# Mixer.net
KiCad netlist of a schematic drawn in EAGLE
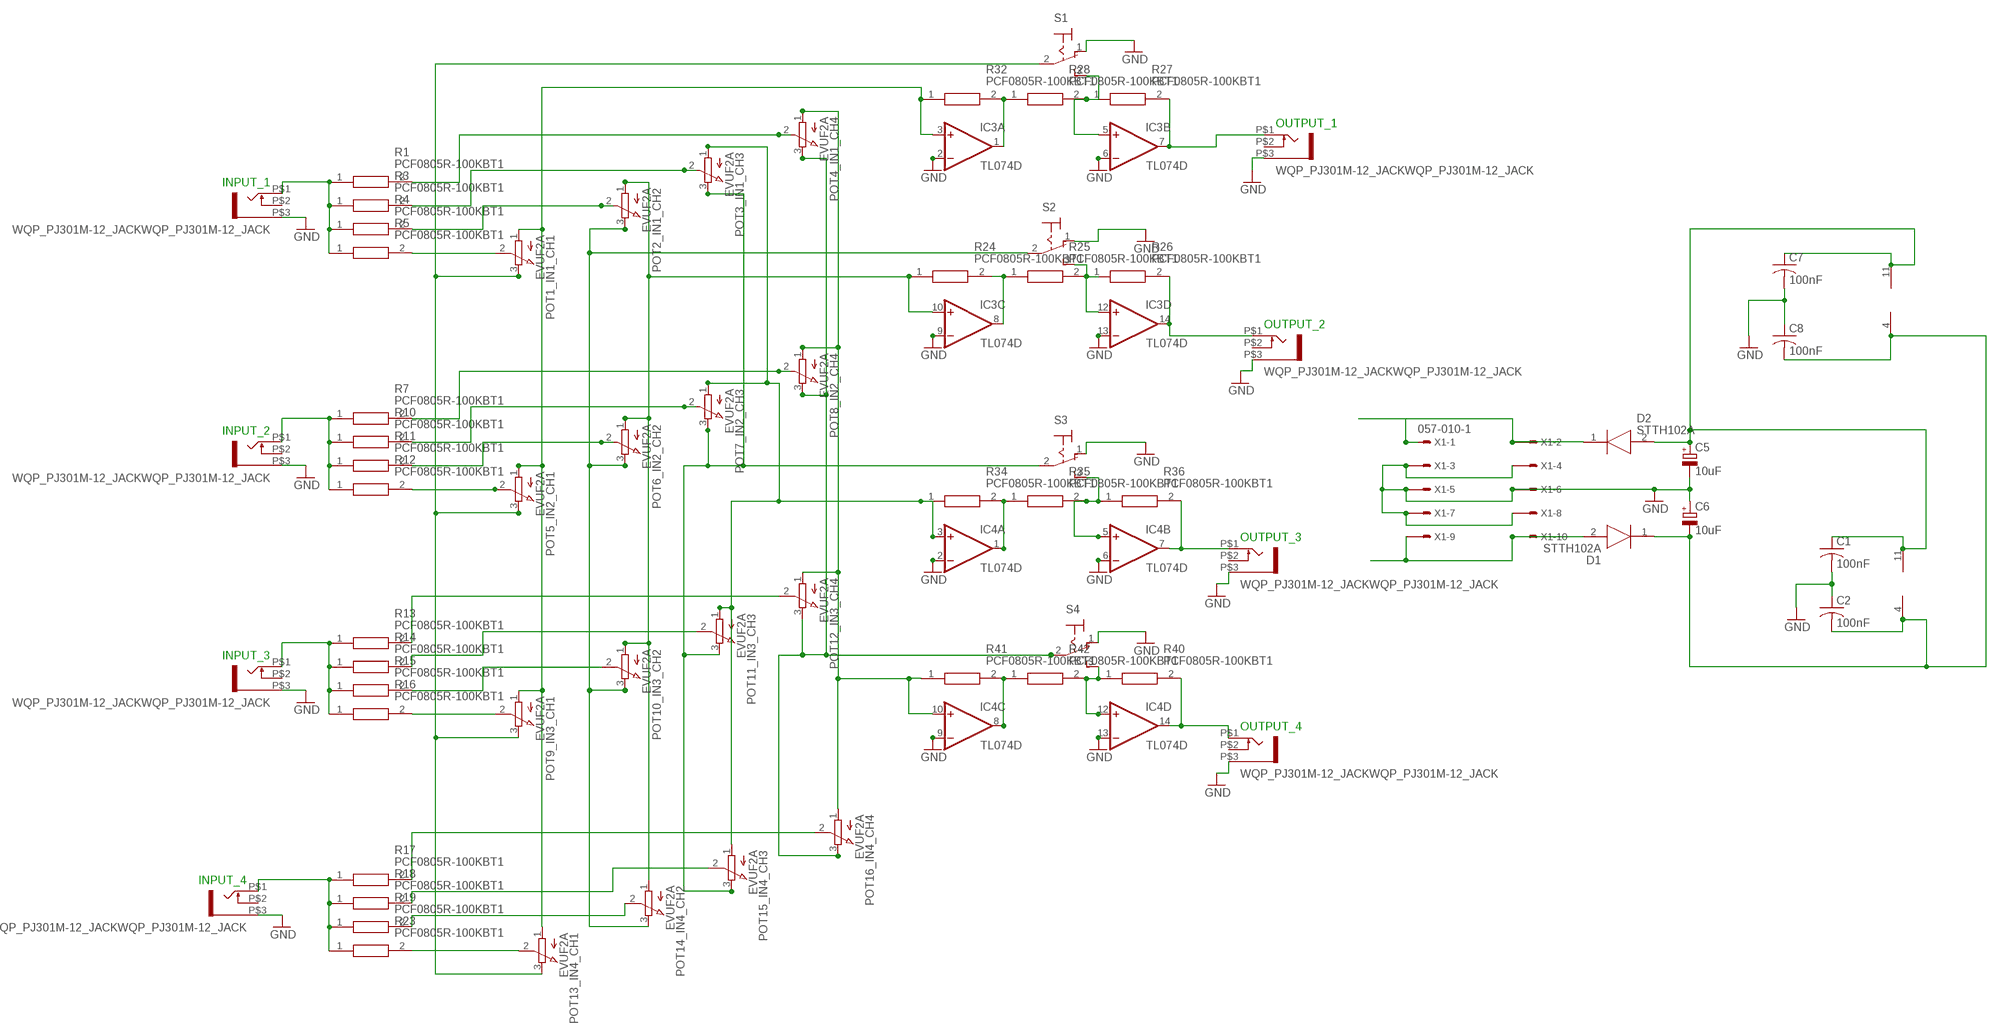
[diagram p0: schematic, sheet 1]

(export (version "E")
  (design (tool "Eeschema 10.0.6"))
  (components
    (comp (ref "C1")
      (value "100nF")
      (footprint "eagle-import:C0805K")
      (libsource (lib "eagle-import") (part "C-USC0805K"))
    )
    (comp (ref "C2")
      (value "100nF")
      (footprint "eagle-import:C0805K")
      (libsource (lib "eagle-import") (part "C-USC0805K"))
    )
    (comp (ref "C5")
      (value "10uF")
      (footprint "eagle-import:153CLV-0605")
      (libsource (lib "eagle-import") (part "CPOL-EU153CLV-0605"))
    )
    (comp (ref "C6")
      (value "10uF")
      (footprint "eagle-import:153CLV-0605")
      (libsource (lib "eagle-import") (part "CPOL-EU153CLV-0605"))
    )
    (comp (ref "C7")
      (value "100nF")
      (footprint "eagle-import:C0805K")
      (libsource (lib "eagle-import") (part "C-USC0805K"))
    )
    (comp (ref "C8")
      (value "100nF")
      (footprint "eagle-import:C0805K")
      (libsource (lib "eagle-import") (part "C-USC0805K"))
    )
    (comp (ref "D1")
      (value "STTH102A")
      (footprint "eagle-import:DIOM5126X265N")
      (libsource (lib "eagle-import") (part "STTH102A"))
    )
    (comp (ref "D2")
      (value "STTH102A")
      (footprint "eagle-import:DIOM5126X265N")
      (libsource (lib "eagle-import") (part "STTH102A"))
    )
    (comp (ref "IC3")
      (value "TL074D")
      (footprint "eagle-import:SO14")
      (libsource (lib "eagle-import") (part "TL074D"))
    )
    (comp (ref "IC4")
      (value "TL074D")
      (footprint "eagle-import:SO14")
      (libsource (lib "eagle-import") (part "TL074D"))
    )
    (comp (ref "INPUT_1")
      (value "WQP_PJ301M-12_JACKWQP_PJ301M-12_JACK")
      (footprint "eagle-import:JACK-3.5")
      (libsource (lib "eagle-import") (part "WQP_PJ301M-12_JACKWQP_PJ301M-12_JACK"))
    )
    (comp (ref "INPUT_2")
      (value "WQP_PJ301M-12_JACKWQP_PJ301M-12_JACK")
      (footprint "eagle-import:JACK-3.5")
      (libsource (lib "eagle-import") (part "WQP_PJ301M-12_JACKWQP_PJ301M-12_JACK"))
    )
    (comp (ref "INPUT_3")
      (value "WQP_PJ301M-12_JACKWQP_PJ301M-12_JACK")
      (footprint "eagle-import:JACK-3.5")
      (libsource (lib "eagle-import") (part "WQP_PJ301M-12_JACKWQP_PJ301M-12_JACK"))
    )
    (comp (ref "INPUT_4")
      (value "WQP_PJ301M-12_JACKWQP_PJ301M-12_JACK")
      (footprint "eagle-import:JACK-3.5")
      (libsource (lib "eagle-import") (part "WQP_PJ301M-12_JACKWQP_PJ301M-12_JACK"))
    )
    (comp (ref "OUTPUT_1")
      (value "WQP_PJ301M-12_JACKWQP_PJ301M-12_JACK")
      (footprint "eagle-import:JACK-3.5")
      (libsource (lib "eagle-import") (part "WQP_PJ301M-12_JACKWQP_PJ301M-12_JACK"))
    )
    (comp (ref "OUTPUT_2")
      (value "WQP_PJ301M-12_JACKWQP_PJ301M-12_JACK")
      (footprint "eagle-import:JACK-3.5")
      (libsource (lib "eagle-import") (part "WQP_PJ301M-12_JACKWQP_PJ301M-12_JACK"))
    )
    (comp (ref "OUTPUT_3")
      (value "WQP_PJ301M-12_JACKWQP_PJ301M-12_JACK")
      (footprint "eagle-import:JACK-3.5")
      (libsource (lib "eagle-import") (part "WQP_PJ301M-12_JACKWQP_PJ301M-12_JACK"))
    )
    (comp (ref "OUTPUT_4")
      (value "WQP_PJ301M-12_JACKWQP_PJ301M-12_JACK")
      (footprint "eagle-import:JACK-3.5")
      (libsource (lib "eagle-import") (part "WQP_PJ301M-12_JACKWQP_PJ301M-12_JACK"))
    )
    (comp (ref "POT1_IN1_CH1")
      (value "EVUF2A")
      (footprint "eagle-import:EVUF")
      (libsource (lib "eagle-import") (part "EVUAF2"))
    )
    (comp (ref "POT2_IN1_CH2")
      (value "EVUF2A")
      (footprint "eagle-import:EVUF")
      (libsource (lib "eagle-import") (part "EVUAF2"))
    )
    (comp (ref "POT3_IN1_CH3")
      (value "EVUF2A")
      (footprint "eagle-import:EVUF")
      (libsource (lib "eagle-import") (part "EVUAF2"))
    )
    (comp (ref "POT4_IN1_CH4")
      (value "EVUF2A")
      (footprint "eagle-import:EVUF")
      (libsource (lib "eagle-import") (part "EVUAF2"))
    )
    (comp (ref "POT5_IN2_CH1")
      (value "EVUF2A")
      (footprint "eagle-import:EVUF")
      (libsource (lib "eagle-import") (part "EVUAF2"))
    )
    (comp (ref "POT6_IN2_CH2")
      (value "EVUF2A")
      (footprint "eagle-import:EVUF")
      (libsource (lib "eagle-import") (part "EVUAF2"))
    )
    (comp (ref "POT7_IN2_CH3")
      (value "EVUF2A")
      (footprint "eagle-import:EVUF")
      (libsource (lib "eagle-import") (part "EVUAF2"))
    )
    (comp (ref "POT8_IN2_CH4")
      (value "EVUF2A")
      (footprint "eagle-import:EVUF")
      (libsource (lib "eagle-import") (part "EVUAF2"))
    )
    (comp (ref "POT9_IN3_CH1")
      (value "EVUF2A")
      (footprint "eagle-import:EVUF")
      (libsource (lib "eagle-import") (part "EVUAF2"))
    )
    (comp (ref "POT10_IN3_CH2")
      (value "EVUF2A")
      (footprint "eagle-import:EVUF")
      (libsource (lib "eagle-import") (part "EVUAF2"))
    )
    (comp (ref "POT11_IN3_CH3")
      (value "EVUF2A")
      (footprint "eagle-import:EVUF")
      (libsource (lib "eagle-import") (part "EVUAF2"))
    )
    (comp (ref "POT12_IN3_CH4")
      (value "EVUF2A")
      (footprint "eagle-import:EVUF")
      (libsource (lib "eagle-import") (part "EVUAF2"))
    )
    (comp (ref "POT13_IN4_CH1")
      (value "EVUF2A")
      (footprint "eagle-import:EVUF")
      (libsource (lib "eagle-import") (part "EVUAF2"))
    )
    (comp (ref "POT14_IN4_CH2")
      (value "EVUF2A")
      (footprint "eagle-import:EVUF")
      (libsource (lib "eagle-import") (part "EVUAF2"))
    )
    (comp (ref "POT15_IN4_CH3")
      (value "EVUF2A")
      (footprint "eagle-import:EVUF")
      (libsource (lib "eagle-import") (part "EVUAF2"))
    )
    (comp (ref "POT16_IN4_CH4")
      (value "EVUF2A")
      (footprint "eagle-import:EVUF")
      (libsource (lib "eagle-import") (part "EVUAF2"))
    )
    (comp (ref "R1")
      (value "PCF0805R-100KBT1")
      (footprint "eagle-import:RESC2012X65N")
      (libsource (lib "eagle-import") (part "PCF0805R-100KBT1"))
    )
    (comp (ref "R3")
      (value "PCF0805R-100KBT1")
      (footprint "eagle-import:RESC2012X65N")
      (libsource (lib "eagle-import") (part "PCF0805R-100KBT1"))
    )
    (comp (ref "R4")
      (value "PCF0805R-100KBT1")
      (footprint "eagle-import:RESC2012X65N")
      (libsource (lib "eagle-import") (part "PCF0805R-100KBT1"))
    )
    (comp (ref "R5")
      (value "PCF0805R-100KBT1")
      (footprint "eagle-import:RESC2012X65N")
      (libsource (lib "eagle-import") (part "PCF0805R-100KBT1"))
    )
    (comp (ref "R7")
      (value "PCF0805R-100KBT1")
      (footprint "eagle-import:RESC2012X65N")
      (libsource (lib "eagle-import") (part "PCF0805R-100KBT1"))
    )
    (comp (ref "R10")
      (value "PCF0805R-100KBT1")
      (footprint "eagle-import:RESC2012X65N")
      (libsource (lib "eagle-import") (part "PCF0805R-100KBT1"))
    )
    (comp (ref "R11")
      (value "PCF0805R-100KBT1")
      (footprint "eagle-import:RESC2012X65N")
      (libsource (lib "eagle-import") (part "PCF0805R-100KBT1"))
    )
    (comp (ref "R12")
      (value "PCF0805R-100KBT1")
      (footprint "eagle-import:RESC2012X65N")
      (libsource (lib "eagle-import") (part "PCF0805R-100KBT1"))
    )
    (comp (ref "R13")
      (value "PCF0805R-100KBT1")
      (footprint "eagle-import:RESC2012X65N")
      (libsource (lib "eagle-import") (part "PCF0805R-100KBT1"))
    )
    (comp (ref "R14")
      (value "PCF0805R-100KBT1")
      (footprint "eagle-import:RESC2012X65N")
      (libsource (lib "eagle-import") (part "PCF0805R-100KBT1"))
    )
    (comp (ref "R15")
      (value "PCF0805R-100KBT1")
      (footprint "eagle-import:RESC2012X65N")
      (libsource (lib "eagle-import") (part "PCF0805R-100KBT1"))
    )
    (comp (ref "R16")
      (value "PCF0805R-100KBT1")
      (footprint "eagle-import:RESC2012X65N")
      (libsource (lib "eagle-import") (part "PCF0805R-100KBT1"))
    )
    (comp (ref "R17")
      (value "PCF0805R-100KBT1")
      (footprint "eagle-import:RESC2012X65N")
      (libsource (lib "eagle-import") (part "PCF0805R-100KBT1"))
    )
    (comp (ref "R18")
      (value "PCF0805R-100KBT1")
      (footprint "eagle-import:RESC2012X65N")
      (libsource (lib "eagle-import") (part "PCF0805R-100KBT1"))
    )
    (comp (ref "R19")
      (value "PCF0805R-100KBT1")
      (footprint "eagle-import:RESC2012X65N")
      (libsource (lib "eagle-import") (part "PCF0805R-100KBT1"))
    )
    (comp (ref "R23")
      (value "PCF0805R-100KBT1")
      (footprint "eagle-import:RESC2012X65N")
      (libsource (lib "eagle-import") (part "PCF0805R-100KBT1"))
    )
    (comp (ref "R24")
      (value "PCF0805R-100KBT1")
      (footprint "eagle-import:RESC2012X65N")
      (libsource (lib "eagle-import") (part "PCF0805R-100KBT1"))
    )
    (comp (ref "R25")
      (value "PCF0805R-100KBT1")
      (footprint "eagle-import:RESC2012X65N")
      (libsource (lib "eagle-import") (part "PCF0805R-100KBT1"))
    )
    (comp (ref "R26")
      (value "PCF0805R-100KBT1")
      (footprint "eagle-import:RESC2012X65N")
      (libsource (lib "eagle-import") (part "PCF0805R-100KBT1"))
    )
    (comp (ref "R27")
      (value "PCF0805R-100KBT1")
      (footprint "eagle-import:RESC2012X65N")
      (libsource (lib "eagle-import") (part "PCF0805R-100KBT1"))
    )
    (comp (ref "R28")
      (value "PCF0805R-100KBT1")
      (footprint "eagle-import:RESC2012X65N")
      (libsource (lib "eagle-import") (part "PCF0805R-100KBT1"))
    )
    (comp (ref "R32")
      (value "PCF0805R-100KBT1")
      (footprint "eagle-import:RESC2012X65N")
      (libsource (lib "eagle-import") (part "PCF0805R-100KBT1"))
    )
    (comp (ref "R34")
      (value "PCF0805R-100KBT1")
      (footprint "eagle-import:RESC2012X65N")
      (libsource (lib "eagle-import") (part "PCF0805R-100KBT1"))
    )
    (comp (ref "R35")
      (value "PCF0805R-100KBT1")
      (footprint "eagle-import:RESC2012X65N")
      (libsource (lib "eagle-import") (part "PCF0805R-100KBT1"))
    )
    (comp (ref "R36")
      (value "PCF0805R-100KBT1")
      (footprint "eagle-import:RESC2012X65N")
      (libsource (lib "eagle-import") (part "PCF0805R-100KBT1"))
    )
    (comp (ref "R40")
      (value "PCF0805R-100KBT1")
      (footprint "eagle-import:RESC2012X65N")
      (libsource (lib "eagle-import") (part "PCF0805R-100KBT1"))
    )
    (comp (ref "R41")
      (value "PCF0805R-100KBT1")
      (footprint "eagle-import:RESC2012X65N")
      (libsource (lib "eagle-import") (part "PCF0805R-100KBT1"))
    )
    (comp (ref "R42")
      (value "PCF0805R-100KBT1")
      (footprint "eagle-import:RESC2012X65N")
      (libsource (lib "eagle-import") (part "PCF0805R-100KBT1"))
    )
    (comp (ref "S1")
      (value "M9040P")
      (footprint "eagle-import:M9040P")
      (libsource (lib "eagle-import") (part "M9040P"))
    )
    (comp (ref "S2")
      (value "M9040P")
      (footprint "eagle-import:M9040P")
      (libsource (lib "eagle-import") (part "M9040P"))
    )
    (comp (ref "S3")
      (value "M9040P")
      (footprint "eagle-import:M9040P")
      (libsource (lib "eagle-import") (part "M9040P"))
    )
    (comp (ref "S4")
      (value "M9040P")
      (footprint "eagle-import:M9040P")
      (libsource (lib "eagle-import") (part "M9040P"))
    )
    (comp (ref "X1")
      (value "057-010-1")
      (footprint "eagle-import:057-010-1")
      (libsource (lib "eagle-import") (part "057-010-1"))
    )
  )
  (nets
    (net (code "1") (name "GND") (class "Default")
      (node (ref "C1") (pin "2") (pinfunction "2_2") (pintype "passive"))
      (node (ref "C2") (pin "1") (pinfunction "1_1") (pintype "passive"))
      (node (ref "C5") (pin "-") (pinfunction "-_-") (pintype "passive"))
      (node (ref "C6") (pin "+") (pinfunction "+_+") (pintype "passive"))
      (node (ref "C7") (pin "2") (pinfunction "2_2") (pintype "passive"))
      (node (ref "C8") (pin "1") (pinfunction "1_1") (pintype "passive"))
      (node (ref "IC3") (pin "13") (pinfunction "-IN_13") (pintype "input"))
      (node (ref "IC3") (pin "2") (pinfunction "-IN_2") (pintype "input"))
      (node (ref "IC3") (pin "6") (pinfunction "-IN_6") (pintype "input"))
      (node (ref "IC3") (pin "9") (pinfunction "-IN_9") (pintype "input"))
      (node (ref "IC4") (pin "13") (pinfunction "-IN_13") (pintype "input"))
      (node (ref "IC4") (pin "2") (pinfunction "-IN_2") (pintype "input"))
      (node (ref "IC4") (pin "6") (pinfunction "-IN_6") (pintype "input"))
      (node (ref "IC4") (pin "9") (pinfunction "-IN_9") (pintype "input"))
      (node (ref "INPUT_1") (pin "P$3") (pinfunction "1_P$3") (pintype "passive"))
      (node (ref "INPUT_2") (pin "P$3") (pinfunction "1_P$3") (pintype "passive"))
      (node (ref "INPUT_3") (pin "P$3") (pinfunction "1_P$3") (pintype "passive"))
      (node (ref "INPUT_4") (pin "P$3") (pinfunction "1_P$3") (pintype "passive"))
      (node (ref "OUTPUT_1") (pin "P$3") (pinfunction "1_P$3") (pintype "passive"))
      (node (ref "OUTPUT_2") (pin "P$3") (pinfunction "1_P$3") (pintype "passive"))
      (node (ref "OUTPUT_3") (pin "P$3") (pinfunction "1_P$3") (pintype "passive"))
      (node (ref "OUTPUT_4") (pin "P$3") (pinfunction "1_P$3") (pintype "passive"))
      (node (ref "S1") (pin "1") (pinfunction "O_1") (pintype "passive"))
      (node (ref "S2") (pin "1") (pinfunction "O_1") (pintype "passive"))
      (node (ref "S3") (pin "1") (pinfunction "O_1") (pintype "passive"))
      (node (ref "S4") (pin "1") (pinfunction "O_1") (pintype "passive"))
      (node (ref "X1") (pin "3") (pinfunction "S_3") (pintype "passive"))
      (node (ref "X1") (pin "4") (pinfunction "S_4") (pintype "passive"))
      (node (ref "X1") (pin "5") (pinfunction "S_5") (pintype "passive"))
      (node (ref "X1") (pin "6") (pinfunction "S_6") (pintype "passive"))
      (node (ref "X1") (pin "7") (pinfunction "S_7") (pintype "passive"))
      (node (ref "X1") (pin "8") (pinfunction "S_8") (pintype "passive"))
    )
    (net (code "2") (name "Net-(D1-A)") (class "Default")
      (node (ref "D1") (pin "2") (pinfunction "A_2") (pintype "bidirectional"))
      (node (ref "X1") (pin "10") (pinfunction "S_10") (pintype "passive"))
      (node (ref "X1") (pin "9") (pinfunction "S_9") (pintype "passive"))
    )
    (net (code "3") (name "Net-(D1-K)") (class "Default")
      (node (ref "C2") (pin "2") (pinfunction "2_2") (pintype "passive"))
      (node (ref "C6") (pin "-") (pinfunction "-_-") (pintype "passive"))
      (node (ref "C8") (pin "2") (pinfunction "2_2") (pintype "passive"))
      (node (ref "D1") (pin "1") (pinfunction "K_1") (pintype "bidirectional"))
      (node (ref "IC3") (pin "4") (pinfunction "V+_4") (pintype "power_in"))
      (node (ref "IC4") (pin "4") (pinfunction "V+_4") (pintype "power_in"))
    )
    (net (code "4") (name "Net-(D2-A)") (class "Default")
      (node (ref "C1") (pin "1") (pinfunction "1_1") (pintype "passive"))
      (node (ref "C5") (pin "+") (pinfunction "+_+") (pintype "passive"))
      (node (ref "C7") (pin "1") (pinfunction "1_1") (pintype "passive"))
      (node (ref "D2") (pin "2") (pinfunction "A_2") (pintype "bidirectional"))
      (node (ref "IC3") (pin "11") (pinfunction "V-_11") (pintype "power_in"))
      (node (ref "IC4") (pin "11") (pinfunction "V-_11") (pintype "power_in"))
    )
    (net (code "5") (name "Net-(D2-K)") (class "Default")
      (node (ref "D2") (pin "1") (pinfunction "K_1") (pintype "bidirectional"))
      (node (ref "X1") (pin "1") (pinfunction "S_1") (pintype "passive"))
      (node (ref "X1") (pin "2") (pinfunction "S_2") (pintype "passive"))
    )
    (net (code "6") (name "Net-(IC3A-+IN)") (class "Default")
      (node (ref "IC3") (pin "3") (pinfunction "+IN_3") (pintype "input"))
      (node (ref "POT13_IN4_CH1") (pin "1") (pinfunction "A_1") (pintype "passive"))
      (node (ref "POT1_IN1_CH1") (pin "1") (pinfunction "A_1") (pintype "passive"))
      (node (ref "POT5_IN2_CH1") (pin "1") (pinfunction "A_1") (pintype "passive"))
      (node (ref "POT9_IN3_CH1") (pin "1") (pinfunction "A_1") (pintype "passive"))
      (node (ref "R32") (pin "1") (pinfunction "1_1") (pintype "bidirectional"))
    )
    (net (code "7") (name "Net-(IC3A-OUT)") (class "Default")
      (node (ref "IC3") (pin "1") (pinfunction "OUT_1") (pintype "output"))
      (node (ref "R28") (pin "1") (pinfunction "1_1") (pintype "bidirectional"))
      (node (ref "R32") (pin "2") (pinfunction "2_2") (pintype "bidirectional"))
    )
    (net (code "8") (name "Net-(IC3B-+IN)") (class "Default")
      (node (ref "IC3") (pin "5") (pinfunction "+IN_5") (pintype "input"))
      (node (ref "R27") (pin "1") (pinfunction "1_1") (pintype "bidirectional"))
      (node (ref "R28") (pin "2") (pinfunction "2_2") (pintype "bidirectional"))
      (node (ref "S1") (pin "3") (pinfunction "S_3") (pintype "passive"))
    )
    (net (code "9") (name "Net-(IC3B-OUT)") (class "Default")
      (node (ref "IC3") (pin "7") (pinfunction "OUT_7") (pintype "output"))
      (node (ref "OUTPUT_1") (pin "P$1") (pinfunction "2_P$1") (pintype "passive"))
      (node (ref "R27") (pin "2") (pinfunction "2_2") (pintype "bidirectional"))
    )
    (net (code "10") (name "Net-(IC3C-+IN)") (class "Default")
      (node (ref "IC3") (pin "10") (pinfunction "+IN_10") (pintype "input"))
      (node (ref "POT10_IN3_CH2") (pin "1") (pinfunction "A_1") (pintype "passive"))
      (node (ref "POT14_IN4_CH2") (pin "1") (pinfunction "A_1") (pintype "passive"))
      (node (ref "POT2_IN1_CH2") (pin "1") (pinfunction "A_1") (pintype "passive"))
      (node (ref "POT6_IN2_CH2") (pin "1") (pinfunction "A_1") (pintype "passive"))
      (node (ref "R24") (pin "1") (pinfunction "1_1") (pintype "bidirectional"))
    )
    (net (code "11") (name "Net-(IC3C-OUT)") (class "Default")
      (node (ref "IC3") (pin "8") (pinfunction "OUT_8") (pintype "output"))
      (node (ref "R24") (pin "2") (pinfunction "2_2") (pintype "bidirectional"))
      (node (ref "R25") (pin "1") (pinfunction "1_1") (pintype "bidirectional"))
    )
    (net (code "12") (name "Net-(IC3D-+IN)") (class "Default")
      (node (ref "IC3") (pin "12") (pinfunction "+IN_12") (pintype "input"))
      (node (ref "R25") (pin "2") (pinfunction "2_2") (pintype "bidirectional"))
      (node (ref "R26") (pin "1") (pinfunction "1_1") (pintype "bidirectional"))
      (node (ref "S2") (pin "3") (pinfunction "S_3") (pintype "passive"))
    )
    (net (code "13") (name "Net-(IC3D-OUT)") (class "Default")
      (node (ref "IC3") (pin "14") (pinfunction "OUT_14") (pintype "output"))
      (node (ref "OUTPUT_2") (pin "P$1") (pinfunction "2_P$1") (pintype "passive"))
      (node (ref "R26") (pin "2") (pinfunction "2_2") (pintype "bidirectional"))
    )
    (net (code "14") (name "Net-(IC4A-+IN)") (class "Default")
      (node (ref "IC4") (pin "3") (pinfunction "+IN_3") (pintype "input"))
      (node (ref "POT11_IN3_CH3") (pin "1") (pinfunction "A_1") (pintype "passive"))
      (node (ref "POT15_IN4_CH3") (pin "1") (pinfunction "A_1") (pintype "passive"))
      (node (ref "POT3_IN1_CH3") (pin "1") (pinfunction "A_1") (pintype "passive"))
      (node (ref "POT7_IN2_CH3") (pin "1") (pinfunction "A_1") (pintype "passive"))
      (node (ref "R34") (pin "1") (pinfunction "1_1") (pintype "bidirectional"))
    )
    (net (code "15") (name "Net-(IC4A-OUT)") (class "Default")
      (node (ref "IC4") (pin "1") (pinfunction "OUT_1") (pintype "output"))
      (node (ref "R34") (pin "2") (pinfunction "2_2") (pintype "bidirectional"))
      (node (ref "R35") (pin "1") (pinfunction "1_1") (pintype "bidirectional"))
    )
    (net (code "16") (name "Net-(IC4B-+IN)") (class "Default")
      (node (ref "IC4") (pin "5") (pinfunction "+IN_5") (pintype "input"))
      (node (ref "R35") (pin "2") (pinfunction "2_2") (pintype "bidirectional"))
      (node (ref "R36") (pin "1") (pinfunction "1_1") (pintype "bidirectional"))
      (node (ref "S3") (pin "3") (pinfunction "S_3") (pintype "passive"))
    )
    (net (code "17") (name "Net-(IC4B-OUT)") (class "Default")
      (node (ref "IC4") (pin "7") (pinfunction "OUT_7") (pintype "output"))
      (node (ref "OUTPUT_3") (pin "P$1") (pinfunction "2_P$1") (pintype "passive"))
      (node (ref "R36") (pin "2") (pinfunction "2_2") (pintype "bidirectional"))
    )
    (net (code "18") (name "Net-(IC4C-+IN)") (class "Default")
      (node (ref "IC4") (pin "10") (pinfunction "+IN_10") (pintype "input"))
      (node (ref "POT12_IN3_CH4") (pin "1") (pinfunction "A_1") (pintype "passive"))
      (node (ref "POT16_IN4_CH4") (pin "1") (pinfunction "A_1") (pintype "passive"))
      (node (ref "POT4_IN1_CH4") (pin "1") (pinfunction "A_1") (pintype "passive"))
      (node (ref "POT8_IN2_CH4") (pin "1") (pinfunction "A_1") (pintype "passive"))
      (node (ref "R41") (pin "1") (pinfunction "1_1") (pintype "bidirectional"))
    )
    (net (code "19") (name "Net-(IC4C-OUT)") (class "Default")
      (node (ref "IC4") (pin "8") (pinfunction "OUT_8") (pintype "output"))
      (node (ref "R41") (pin "2") (pinfunction "2_2") (pintype "bidirectional"))
      (node (ref "R42") (pin "1") (pinfunction "1_1") (pintype "bidirectional"))
    )
    (net (code "20") (name "Net-(IC4D-+IN)") (class "Default")
      (node (ref "IC4") (pin "12") (pinfunction "+IN_12") (pintype "input"))
      (node (ref "R40") (pin "1") (pinfunction "1_1") (pintype "bidirectional"))
      (node (ref "R42") (pin "2") (pinfunction "2_2") (pintype "bidirectional"))
      (node (ref "S4") (pin "3") (pinfunction "S_3") (pintype "passive"))
    )
    (net (code "21") (name "Net-(IC4D-OUT)") (class "Default")
      (node (ref "IC4") (pin "14") (pinfunction "OUT_14") (pintype "output"))
      (node (ref "OUTPUT_4") (pin "P$1") (pinfunction "2_P$1") (pintype "passive"))
      (node (ref "R40") (pin "2") (pinfunction "2_2") (pintype "bidirectional"))
    )
    (net (code "22") (name "Net-(INPUT_1-2)") (class "Default")
      (node (ref "INPUT_1") (pin "P$1") (pinfunction "2_P$1") (pintype "passive"))
      (node (ref "R1") (pin "1") (pinfunction "1_1") (pintype "bidirectional"))
      (node (ref "R3") (pin "1") (pinfunction "1_1") (pintype "bidirectional"))
      (node (ref "R4") (pin "1") (pinfunction "1_1") (pintype "bidirectional"))
      (node (ref "R5") (pin "1") (pinfunction "1_1") (pintype "bidirectional"))
    )
    (net (code "23") (name "Net-(INPUT_2-2)") (class "Default")
      (node (ref "INPUT_2") (pin "P$1") (pinfunction "2_P$1") (pintype "passive"))
      (node (ref "R10") (pin "1") (pinfunction "1_1") (pintype "bidirectional"))
      (node (ref "R11") (pin "1") (pinfunction "1_1") (pintype "bidirectional"))
      (node (ref "R12") (pin "1") (pinfunction "1_1") (pintype "bidirectional"))
      (node (ref "R7") (pin "1") (pinfunction "1_1") (pintype "bidirectional"))
    )
    (net (code "24") (name "Net-(INPUT_3-2)") (class "Default")
      (node (ref "INPUT_3") (pin "P$1") (pinfunction "2_P$1") (pintype "passive"))
      (node (ref "R13") (pin "1") (pinfunction "1_1") (pintype "bidirectional"))
      (node (ref "R14") (pin "1") (pinfunction "1_1") (pintype "bidirectional"))
      (node (ref "R15") (pin "1") (pinfunction "1_1") (pintype "bidirectional"))
      (node (ref "R16") (pin "1") (pinfunction "1_1") (pintype "bidirectional"))
    )
    (net (code "25") (name "Net-(INPUT_4-2)") (class "Default")
      (node (ref "INPUT_4") (pin "P$1") (pinfunction "2_P$1") (pintype "passive"))
      (node (ref "R17") (pin "1") (pinfunction "1_1") (pintype "bidirectional"))
      (node (ref "R18") (pin "1") (pinfunction "1_1") (pintype "bidirectional"))
      (node (ref "R19") (pin "1") (pinfunction "1_1") (pintype "bidirectional"))
      (node (ref "R23") (pin "1") (pinfunction "1_1") (pintype "bidirectional"))
    )
    (net (code "26") (name "Net-(POT1_IN1_CH1-S)") (class "Default")
      (node (ref "POT1_IN1_CH1") (pin "2") (pinfunction "S_2") (pintype "passive"))
      (node (ref "R5") (pin "2") (pinfunction "2_2") (pintype "bidirectional"))
    )
    (net (code "27") (name "Net-(POT2_IN1_CH2-S)") (class "Default")
      (node (ref "POT2_IN1_CH2") (pin "2") (pinfunction "S_2") (pintype "passive"))
      (node (ref "R4") (pin "2") (pinfunction "2_2") (pintype "bidirectional"))
    )
    (net (code "28") (name "Net-(POT3_IN1_CH3-S)") (class "Default")
      (node (ref "POT3_IN1_CH3") (pin "2") (pinfunction "S_2") (pintype "passive"))
      (node (ref "R3") (pin "2") (pinfunction "2_2") (pintype "bidirectional"))
    )
    (net (code "29") (name "Net-(POT4_IN1_CH4-S)") (class "Default")
      (node (ref "POT4_IN1_CH4") (pin "2") (pinfunction "S_2") (pintype "passive"))
      (node (ref "R1") (pin "2") (pinfunction "2_2") (pintype "bidirectional"))
    )
    (net (code "30") (name "Net-(POT5_IN2_CH1-S)") (class "Default")
      (node (ref "POT5_IN2_CH1") (pin "2") (pinfunction "S_2") (pintype "passive"))
      (node (ref "R12") (pin "2") (pinfunction "2_2") (pintype "bidirectional"))
    )
    (net (code "31") (name "Net-(POT6_IN2_CH2-S)") (class "Default")
      (node (ref "POT6_IN2_CH2") (pin "2") (pinfunction "S_2") (pintype "passive"))
      (node (ref "R11") (pin "2") (pinfunction "2_2") (pintype "bidirectional"))
    )
    (net (code "32") (name "Net-(POT7_IN2_CH3-S)") (class "Default")
      (node (ref "POT7_IN2_CH3") (pin "2") (pinfunction "S_2") (pintype "passive"))
      (node (ref "R10") (pin "2") (pinfunction "2_2") (pintype "bidirectional"))
    )
    (net (code "33") (name "Net-(POT8_IN2_CH4-S)") (class "Default")
      (node (ref "POT8_IN2_CH4") (pin "2") (pinfunction "S_2") (pintype "passive"))
      (node (ref "R7") (pin "2") (pinfunction "2_2") (pintype "bidirectional"))
    )
    (net (code "34") (name "Net-(POT9_IN3_CH1-S)") (class "Default")
      (node (ref "POT9_IN3_CH1") (pin "2") (pinfunction "S_2") (pintype "passive"))
      (node (ref "R16") (pin "2") (pinfunction "2_2") (pintype "bidirectional"))
    )
    (net (code "35") (name "Net-(POT10_IN3_CH2-E)") (class "Default")
      (node (ref "POT10_IN3_CH2") (pin "3") (pinfunction "E_3") (pintype "passive"))
      (node (ref "POT14_IN4_CH2") (pin "3") (pinfunction "E_3") (pintype "passive"))
      (node (ref "POT2_IN1_CH2") (pin "3") (pinfunction "E_3") (pintype "passive"))
      (node (ref "POT6_IN2_CH2") (pin "3") (pinfunction "E_3") (pintype "passive"))
      (node (ref "S2") (pin "2") (pinfunction "P_2") (pintype "passive"))
    )
    (net (code "36") (name "Net-(POT10_IN3_CH2-S)") (class "Default")
      (node (ref "POT10_IN3_CH2") (pin "2") (pinfunction "S_2") (pintype "passive"))
      (node (ref "R15") (pin "2") (pinfunction "2_2") (pintype "bidirectional"))
    )
    (net (code "37") (name "Net-(POT11_IN3_CH3-E)") (class "Default")
      (node (ref "POT11_IN3_CH3") (pin "3") (pinfunction "E_3") (pintype "passive"))
      (node (ref "POT15_IN4_CH3") (pin "3") (pinfunction "E_3") (pintype "passive"))
      (node (ref "POT3_IN1_CH3") (pin "3") (pinfunction "E_3") (pintype "passive"))
      (node (ref "POT7_IN2_CH3") (pin "3") (pinfunction "E_3") (pintype "passive"))
      (node (ref "S3") (pin "2") (pinfunction "P_2") (pintype "passive"))
    )
    (net (code "38") (name "Net-(POT11_IN3_CH3-S)") (class "Default")
      (node (ref "POT11_IN3_CH3") (pin "2") (pinfunction "S_2") (pintype "passive"))
      (node (ref "R14") (pin "2") (pinfunction "2_2") (pintype "bidirectional"))
    )
    (net (code "39") (name "Net-(POT12_IN3_CH4-E)") (class "Default")
      (node (ref "POT12_IN3_CH4") (pin "3") (pinfunction "E_3") (pintype "passive"))
      (node (ref "POT16_IN4_CH4") (pin "3") (pinfunction "E_3") (pintype "passive"))
      (node (ref "POT4_IN1_CH4") (pin "3") (pinfunction "E_3") (pintype "passive"))
      (node (ref "POT8_IN2_CH4") (pin "3") (pinfunction "E_3") (pintype "passive"))
      (node (ref "S4") (pin "2") (pinfunction "P_2") (pintype "passive"))
    )
    (net (code "40") (name "Net-(POT12_IN3_CH4-S)") (class "Default")
      (node (ref "POT12_IN3_CH4") (pin "2") (pinfunction "S_2") (pintype "passive"))
      (node (ref "R13") (pin "2") (pinfunction "2_2") (pintype "bidirectional"))
    )
    (net (code "41") (name "Net-(POT13_IN4_CH1-E)") (class "Default")
      (node (ref "POT13_IN4_CH1") (pin "3") (pinfunction "E_3") (pintype "passive"))
      (node (ref "POT1_IN1_CH1") (pin "3") (pinfunction "E_3") (pintype "passive"))
      (node (ref "POT5_IN2_CH1") (pin "3") (pinfunction "E_3") (pintype "passive"))
      (node (ref "POT9_IN3_CH1") (pin "3") (pinfunction "E_3") (pintype "passive"))
      (node (ref "S1") (pin "2") (pinfunction "P_2") (pintype "passive"))
    )
    (net (code "42") (name "Net-(POT13_IN4_CH1-S)") (class "Default")
      (node (ref "POT13_IN4_CH1") (pin "2") (pinfunction "S_2") (pintype "passive"))
      (node (ref "R23") (pin "2") (pinfunction "2_2") (pintype "bidirectional"))
    )
    (net (code "43") (name "Net-(POT14_IN4_CH2-S)") (class "Default")
      (node (ref "POT14_IN4_CH2") (pin "2") (pinfunction "S_2") (pintype "passive"))
      (node (ref "R19") (pin "2") (pinfunction "2_2") (pintype "bidirectional"))
    )
    (net (code "44") (name "Net-(POT15_IN4_CH3-S)") (class "Default")
      (node (ref "POT15_IN4_CH3") (pin "2") (pinfunction "S_2") (pintype "passive"))
      (node (ref "R18") (pin "2") (pinfunction "2_2") (pintype "bidirectional"))
    )
    (net (code "45") (name "Net-(POT16_IN4_CH4-S)") (class "Default")
      (node (ref "POT16_IN4_CH4") (pin "2") (pinfunction "S_2") (pintype "passive"))
      (node (ref "R17") (pin "2") (pinfunction "2_2") (pintype "bidirectional"))
    )
    (net (code "46") (name "unconnected-(INPUT_1-3-PadP$2)") (class "Default")
      (node (ref "INPUT_1") (pin "P$2") (pinfunction "3_P$2") (pintype "passive"))
    )
    (net (code "47") (name "unconnected-(INPUT_2-3-PadP$2)") (class "Default")
      (node (ref "INPUT_2") (pin "P$2") (pinfunction "3_P$2") (pintype "passive"))
    )
    (net (code "48") (name "unconnected-(INPUT_3-3-PadP$2)") (class "Default")
      (node (ref "INPUT_3") (pin "P$2") (pinfunction "3_P$2") (pintype "passive"))
    )
    (net (code "49") (name "unconnected-(INPUT_4-3-PadP$2)") (class "Default")
      (node (ref "INPUT_4") (pin "P$2") (pinfunction "3_P$2") (pintype "passive"))
    )
    (net (code "50") (name "unconnected-(OUTPUT_1-3-PadP$2)") (class "Default")
      (node (ref "OUTPUT_1") (pin "P$2") (pinfunction "3_P$2") (pintype "passive"))
    )
    (net (code "51") (name "unconnected-(OUTPUT_2-3-PadP$2)") (class "Default")
      (node (ref "OUTPUT_2") (pin "P$2") (pinfunction "3_P$2") (pintype "passive"))
    )
    (net (code "52") (name "unconnected-(OUTPUT_3-3-PadP$2)") (class "Default")
      (node (ref "OUTPUT_3") (pin "P$2") (pinfunction "3_P$2") (pintype "passive"))
    )
    (net (code "53") (name "unconnected-(OUTPUT_4-3-PadP$2)") (class "Default")
      (node (ref "OUTPUT_4") (pin "P$2") (pinfunction "3_P$2") (pintype "passive"))
    )
  )
)
